# SMD_FTDI.net
KiCad netlist of a schematic drawn in EAGLE
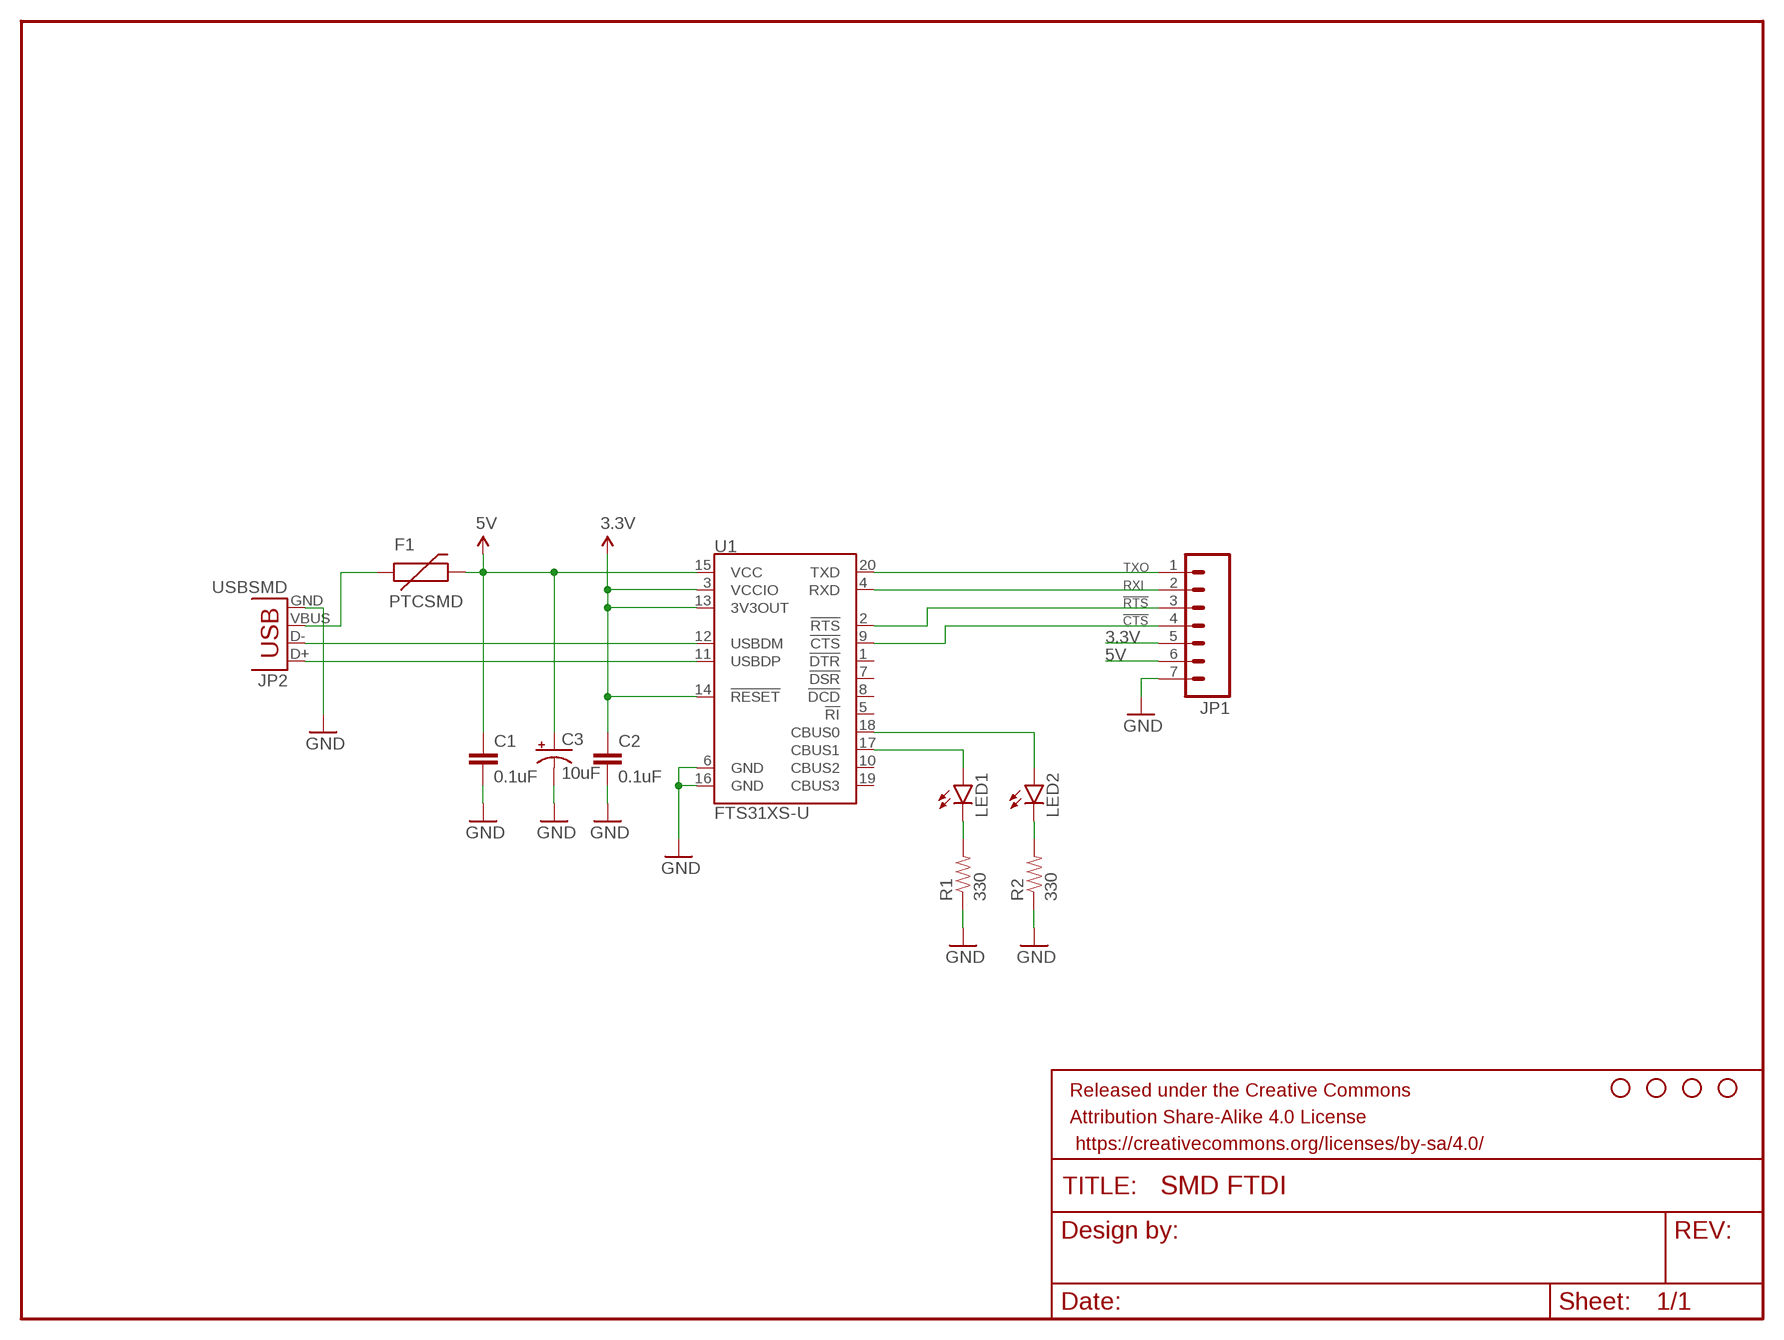
[diagram p0: schematic, sheet 1]

(export (version "E")
  (design (tool "Eeschema 10.0.6"))
  (components
    (comp (ref "C1")
      (value "0.1uF")
      (footprint "eagle-import:0603-CAP")
      (libsource (lib "eagle-import") (part "CAP0603-CAP"))
    )
    (comp (ref "C2")
      (value "0.1uF")
      (footprint "eagle-import:0603-CAP")
      (libsource (lib "eagle-import") (part "CAP0603-CAP"))
    )
    (comp (ref "C3")
      (value "10uF")
      (footprint "eagle-import:EIA3216-KIT")
      (libsource (lib "eagle-import") (part "CAP_POL1206-KIT"))
    )
    (comp (ref "F1")
      (value "PTCSMD")
      (footprint "eagle-import:PTC-1206")
      (libsource (lib "eagle-import") (part "PTCSMD"))
    )
    (comp (ref "FRAME1")
      (value "FRAME-LETTER")
      (footprint "eagle-import:CREATIVE_COMMONS")
      (fields (field (name "DESIGNER") "NAME"))
      (libsource (lib "eagle-import") (part "FRAME-LETTER"))
    )
    (comp (ref "JP1")
      (value "M07")
      (footprint "eagle-import:1X07")
      (libsource (lib "eagle-import") (part "M07"))
    )
    (comp (ref "JP2")
      (value "USBSMD")
      (footprint "eagle-import:USB-MINIB")
      (libsource (lib "eagle-import") (part "USBSMD"))
    )
    (comp (ref "LED1")
      (value "LED0603")
      (footprint "eagle-import:LED-0603")
      (libsource (lib "eagle-import") (part "LED0603"))
    )
    (comp (ref "LED2")
      (value "LED0603")
      (footprint "eagle-import:LED-0603")
      (libsource (lib "eagle-import") (part "LED0603"))
    )
    (comp (ref "R1")
      (value "330")
      (footprint "eagle-import:0603-RES")
      (libsource (lib "eagle-import") (part "RESISTOR0603-RES"))
    )
    (comp (ref "R2")
      (value "330")
      (footprint "eagle-import:0603-RES")
      (libsource (lib "eagle-import") (part "RESISTOR0603-RES"))
    )
    (comp (ref "STANDOFF1")
      (value "STAND-OFF")
      (footprint "eagle-import:STAND-OFF")
      (libsource (lib "eagle-import") (part "STAND-OFF"))
    )
    (comp (ref "STANDOFF2")
      (value "STAND-OFF")
      (footprint "eagle-import:STAND-OFF")
      (libsource (lib "eagle-import") (part "STAND-OFF"))
    )
    (comp (ref "STANDOFF3")
      (value "STAND-OFF")
      (footprint "eagle-import:STAND-OFF")
      (libsource (lib "eagle-import") (part "STAND-OFF"))
    )
    (comp (ref "STANDOFF4")
      (value "STAND-OFF")
      (footprint "eagle-import:STAND-OFF")
      (libsource (lib "eagle-import") (part "STAND-OFF"))
    )
    (comp (ref "U1")
      (value "FTS31XS-U")
      (footprint "eagle-import:SSOP20_L")
      (libsource (lib "eagle-import") (part "FT231XS"))
    )
  )
  (nets
    (net (code "1") (name "/RXI") (class "Default")
      (node (ref "JP1") (pin "2") (pinfunction "2_2") (pintype "passive"))
      (node (ref "U1") (pin "4") (pinfunction "RXD_4") (pintype "bidirectional"))
    )
    (net (code "2") (name "/TXO") (class "Default")
      (node (ref "JP1") (pin "1") (pinfunction "1_1") (pintype "passive"))
      (node (ref "U1") (pin "20") (pinfunction "TXD_20") (pintype "bidirectional"))
    )
    (net (code "3") (name "/~{CTS}") (class "Default")
      (node (ref "JP1") (pin "4") (pinfunction "4_4") (pintype "passive"))
      (node (ref "U1") (pin "9") (pinfunction "~{CTS}_9") (pintype "bidirectional"))
    )
    (net (code "4") (name "/~{RTS}") (class "Default")
      (node (ref "JP1") (pin "3") (pinfunction "3_3") (pintype "passive"))
      (node (ref "U1") (pin "2") (pinfunction "~{RTS}_2") (pintype "bidirectional"))
    )
    (net (code "5") (name "3.3V") (class "Default")
      (node (ref "C2") (pin "1") (pinfunction "1_1") (pintype "passive"))
      (node (ref "JP1") (pin "5") (pinfunction "5_5") (pintype "passive"))
      (node (ref "U1") (pin "13") (pinfunction "3V3OUT_13") (pintype "bidirectional"))
      (node (ref "U1") (pin "14") (pinfunction "~{RESET}_14") (pintype "bidirectional"))
      (node (ref "U1") (pin "3") (pinfunction "VCCIO_3") (pintype "bidirectional"))
    )
    (net (code "6") (name "5V") (class "Default")
      (node (ref "C1") (pin "1") (pinfunction "1_1") (pintype "passive"))
      (node (ref "C3") (pin "A") (pinfunction "+_A") (pintype "passive"))
      (node (ref "F1") (pin "2") (pinfunction "2_2") (pintype "bidirectional"))
      (node (ref "JP1") (pin "6") (pinfunction "6_6") (pintype "passive"))
      (node (ref "U1") (pin "15") (pinfunction "VCC_15") (pintype "bidirectional"))
    )
    (net (code "7") (name "GND") (class "Default")
      (node (ref "C1") (pin "2") (pinfunction "2_2") (pintype "passive"))
      (node (ref "C2") (pin "2") (pinfunction "2_2") (pintype "passive"))
      (node (ref "C3") (pin "C") (pinfunction "-_C") (pintype "passive"))
      (node (ref "JP1") (pin "7") (pinfunction "7_7") (pintype "passive"))
      (node (ref "JP2") (pin "GND") (pinfunction "GND_GND") (pintype "bidirectional"))
      (node (ref "R1") (pin "1") (pinfunction "1_1") (pintype "passive"))
      (node (ref "R2") (pin "1") (pinfunction "1_1") (pintype "passive"))
      (node (ref "U1") (pin "16") (pinfunction "GND_16") (pintype "bidirectional"))
      (node (ref "U1") (pin "6") (pinfunction "GND_6") (pintype "bidirectional"))
    )
    (net (code "8") (name "Net-(F1-Pad1)") (class "Default")
      (node (ref "F1") (pin "1") (pinfunction "1_1") (pintype "bidirectional"))
      (node (ref "JP2") (pin "VBUS") (pinfunction "VBUS_VBUS") (pintype "bidirectional"))
    )
    (net (code "9") (name "Net-(LED1-PadC)") (class "Default")
      (node (ref "LED1") (pin "C") (pinfunction "C_C") (pintype "passive"))
      (node (ref "R1") (pin "2") (pinfunction "2_2") (pintype "passive"))
    )
    (net (code "10") (name "Net-(LED2-PadC)") (class "Default")
      (node (ref "LED2") (pin "C") (pinfunction "C_C") (pintype "passive"))
      (node (ref "R2") (pin "2") (pinfunction "2_2") (pintype "passive"))
    )
    (net (code "11") (name "Net-(U1-CBUS0)") (class "Default")
      (node (ref "LED2") (pin "A") (pinfunction "A_A") (pintype "passive"))
      (node (ref "U1") (pin "18") (pinfunction "CBUS0_18") (pintype "bidirectional"))
    )
    (net (code "12") (name "Net-(U1-CBUS1)") (class "Default")
      (node (ref "LED1") (pin "A") (pinfunction "A_A") (pintype "passive"))
      (node (ref "U1") (pin "17") (pinfunction "CBUS1_17") (pintype "bidirectional"))
    )
    (net (code "13") (name "Net-(U1-USBDM)") (class "Default")
      (node (ref "JP2") (pin "D-") (pinfunction "D-_D-") (pintype "bidirectional"))
      (node (ref "U1") (pin "12") (pinfunction "USBDM_12") (pintype "bidirectional"))
    )
    (net (code "14") (name "Net-(U1-USBDP)") (class "Default")
      (node (ref "JP2") (pin "D+") (pinfunction "D+_D+") (pintype "bidirectional"))
      (node (ref "U1") (pin "11") (pinfunction "USBDP_11") (pintype "bidirectional"))
    )
    (net (code "15") (name "unconnected-(U1-CBUS2-Pad10)") (class "Default")
      (node (ref "U1") (pin "10") (pinfunction "CBUS2_10") (pintype "bidirectional"))
    )
    (net (code "16") (name "unconnected-(U1-CBUS3-Pad19)") (class "Default")
      (node (ref "U1") (pin "19") (pinfunction "CBUS3_19") (pintype "bidirectional"))
    )
    (net (code "17") (name "unconnected-(U1-~{DCD}-Pad8)") (class "Default")
      (node (ref "U1") (pin "8") (pinfunction "~{DCD}_8") (pintype "bidirectional"))
    )
    (net (code "18") (name "unconnected-(U1-~{DSR}-Pad7)") (class "Default")
      (node (ref "U1") (pin "7") (pinfunction "~{DSR}_7") (pintype "bidirectional"))
    )
    (net (code "19") (name "unconnected-(U1-~{DTR}-Pad1)") (class "Default")
      (node (ref "U1") (pin "1") (pinfunction "~{DTR}_1") (pintype "bidirectional"))
    )
    (net (code "20") (name "unconnected-(U1-~{RI}-Pad5)") (class "Default")
      (node (ref "U1") (pin "5") (pinfunction "~{RI}_5") (pintype "bidirectional"))
    )
  )
)
